# SZG-TEMPLATE-TXR.net
KiCad netlist of a schematic drawn in Altium Designer
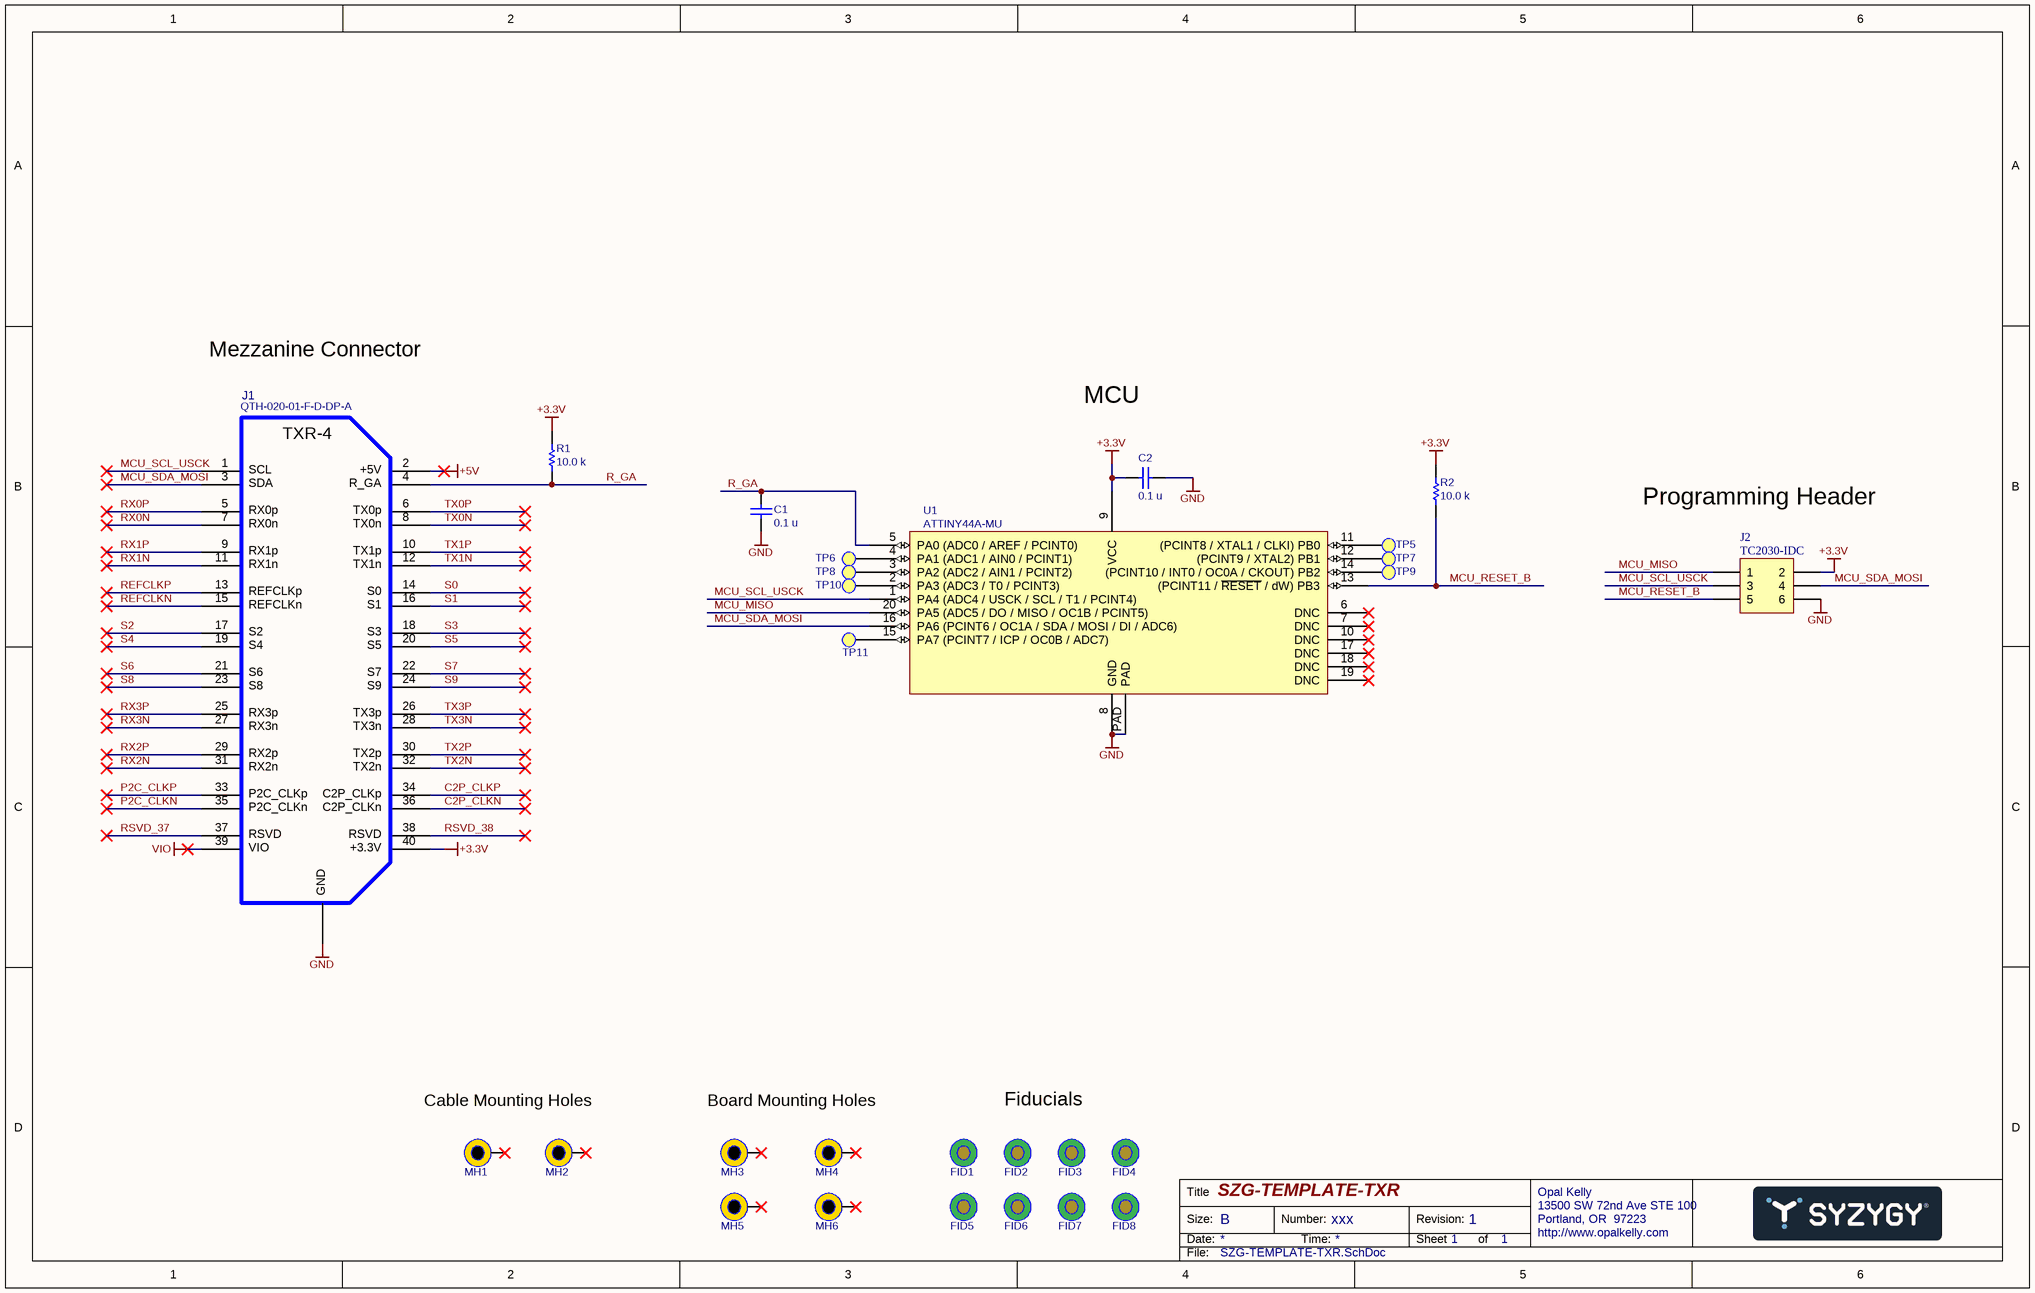
[diagram p0: SZG-TEMPLATE-TXR.SchDoc]

(export (version "E")
  (design (tool "Eeschema 10.0.6"))
  (components
    (comp (ref "C1")
      (value "0.1 u")
      (footprint "CAPC1005X06N")
      (description "Ceramic capacitor")
      (fields (field (name "MANUFACTURER") "Kemet") (field (name "PARTNUMBER") "000070"))
      (libsource (lib "Aligni") (part "Capacitor"))
    )
    (comp (ref "C2")
      (value "0.1 u")
      (footprint "CAPC1005X06N")
      (description "Ceramic capacitor")
      (fields (field (name "MANUFACTURER") "Kemet") (field (name "PARTNUMBER") "000070"))
      (libsource (lib "Aligni") (part "Capacitor"))
    )
    (comp (ref "FID1")
      (value "FIDUCIAL")
      (footprint "FID1MM/2MM-SS")
      (description "PCB fiducial")
      (libsource (lib "NoBOM") (part "FIDUCIAL"))
    )
    (comp (ref "FID2")
      (value "FIDUCIAL")
      (footprint "FID1MM/2MM-SS")
      (description "PCB fiducial")
      (libsource (lib "NoBOM") (part "FIDUCIAL"))
    )
    (comp (ref "FID3")
      (value "FIDUCIAL")
      (footprint "FID1MM/2MM-SS")
      (description "PCB fiducial")
      (libsource (lib "NoBOM") (part "FIDUCIAL"))
    )
    (comp (ref "FID4")
      (value "FIDUCIAL")
      (footprint "FID1MM/2MM-SS")
      (description "PCB fiducial")
      (libsource (lib "NoBOM") (part "FIDUCIAL"))
    )
    (comp (ref "FID5")
      (value "FIDUCIAL")
      (footprint "FID1MM/2MM-SS")
      (description "PCB fiducial")
      (libsource (lib "NoBOM") (part "FIDUCIAL"))
    )
    (comp (ref "FID6")
      (value "FIDUCIAL")
      (footprint "FID1MM/2MM-SS")
      (description "PCB fiducial")
      (libsource (lib "NoBOM") (part "FIDUCIAL"))
    )
    (comp (ref "FID7")
      (value "FIDUCIAL")
      (footprint "FID1MM/2MM-SS")
      (description "PCB fiducial")
      (libsource (lib "NoBOM") (part "FIDUCIAL"))
    )
    (comp (ref "FID8")
      (value "FIDUCIAL")
      (footprint "FID1MM/2MM-SS")
      (description "PCB fiducial")
      (libsource (lib "NoBOM") (part "FIDUCIAL"))
    )
    (comp (ref "J1")
      (value "40-pin, ground protection in middle")
      (footprint "QTH-020-01-X-D-DP-A-L")
      (description "0.5mm hi-speed, high-density header (female)")
      (fields
        (field (name "MANUFACTURER") "Samtec")
        (field (name "MANUFACTURER_PN") "QTH-020-01-F-D-DP-A")
        (field (name "ALIGNIPARTNUMBER") "001605")
      )
      (libsource (lib "Aligni") (part "QTH-DP_QSH-DP-020"))
    )
    (comp (ref "J2")
      (value "~")
      (footprint "TC2030-DUAL")
      (description "Tag-Connect 6-pin Plug-of-Nails spring-pin cable footprint")
      (fields
        (field (name "ALIGNIPARTNUMBER") "002062")
        (field (name "MANUFACTURER") "Tag-Connect")
        (field (name "MANUFACTURER_PN") "TC2030-IDC")
      )
      (libsource (lib "Aligni") (part "Header 3X2"))
    )
    (comp (ref "MH1")
      (value "MTG")
      (footprint "MTG-3.2/6.5-PTH")
      (description "Mounting hole")
      (libsource (lib "NoBOM") (part "MTG"))
    )
    (comp (ref "MH2")
      (value "MTG")
      (footprint "MTG-3.2/6.5-PTH")
      (description "Mounting hole")
      (libsource (lib "NoBOM") (part "MTG"))
    )
    (comp (ref "MH3")
      (value "MTG")
      (footprint "MTG-3.2/6.5-PTH")
      (description "Mounting hole")
      (libsource (lib "NoBOM") (part "MTG"))
    )
    (comp (ref "MH4")
      (value "MTG")
      (footprint "MTG-3.2/6.5-PTH")
      (description "Mounting hole")
      (libsource (lib "NoBOM") (part "MTG"))
    )
    (comp (ref "MH5")
      (value "MTG")
      (footprint "MTG-3.2/6.5-PTH")
      (description "Mounting hole")
      (libsource (lib "NoBOM") (part "MTG"))
    )
    (comp (ref "MH6")
      (value "MTG")
      (footprint "MTG-3.2/6.5-PTH")
      (description "Mounting hole")
      (libsource (lib "NoBOM") (part "MTG"))
    )
    (comp (ref "R1")
      (value "10.0 k")
      (footprint "RESC1005X06N")
      (description "Thick-film resistor")
      (fields (field (name "MANUFACTURER") "Vishay") (field (name "PARTNUMBER") "001521"))
      (libsource (lib "Aligni") (part "Resistor"))
    )
    (comp (ref "R2")
      (value "10.0 k")
      (footprint "RESC1005X06N")
      (description "Thick-film resistor")
      (fields (field (name "MANUFACTURER") "Vishay") (field (name "PARTNUMBER") "001521"))
      (libsource (lib "Aligni") (part "Resistor"))
    )
    (comp (ref "TP5")
      (value "TESTPOINT-SMD20")
      (footprint "TP-SMD20")
      (description "Test point, surface-mount, 20mil")
      (libsource (lib "NoBOM") (part "TESTPOINT-SMD20"))
    )
    (comp (ref "TP6")
      (value "TESTPOINT-SMD20")
      (footprint "TP-SMD20")
      (description "Test point, surface-mount, 20mil")
      (libsource (lib "NoBOM") (part "TESTPOINT-SMD20"))
    )
    (comp (ref "TP7")
      (value "TESTPOINT-SMD20")
      (footprint "TP-SMD20")
      (description "Test point, surface-mount, 20mil")
      (libsource (lib "NoBOM") (part "TESTPOINT-SMD20"))
    )
    (comp (ref "TP8")
      (value "TESTPOINT-SMD20")
      (footprint "TP-SMD20")
      (description "Test point, surface-mount, 20mil")
      (libsource (lib "NoBOM") (part "TESTPOINT-SMD20"))
    )
    (comp (ref "TP9")
      (value "TESTPOINT-SMD20")
      (footprint "TP-SMD20")
      (description "Test point, surface-mount, 20mil")
      (libsource (lib "NoBOM") (part "TESTPOINT-SMD20"))
    )
    (comp (ref "TP10")
      (value "TESTPOINT-SMD20")
      (footprint "TP-SMD20")
      (description "Test point, surface-mount, 20mil")
      (libsource (lib "NoBOM") (part "TESTPOINT-SMD20"))
    )
    (comp (ref "TP11")
      (value "TESTPOINT-SMD20")
      (footprint "TP-SMD20")
      (description "Test point, surface-mount, 20mil")
      (libsource (lib "NoBOM") (part "TESTPOINT-SMD20"))
    )
    (comp (ref "U1")
      (value "ATTINY44A-MU")
      (footprint "QFN-EP-20")
      (description "8-bit MCU, 4 KB flash, 256 bytes EEPROM")
      (fields (field (name "MANUFACTURER") "Microchip") (field (name "PARTNUMBER") "001552"))
      (libsource (lib "Aligni") (part "ATTINYx4A-MU"))
    )
  )
  (nets
    (net (code "1") (name "+3.3V") (class "Default")
      (node (ref "C2") (pin "2") (pinfunction "2_2") (pintype "passive"))
      (node (ref "J1") (pin "40") (pinfunction "40_40") (pintype "passive"))
      (node (ref "J2") (pin "2") (pinfunction "2_2") (pintype "passive"))
      (node (ref "R1") (pin "2") (pinfunction "2_2") (pintype "passive"))
      (node (ref "R2") (pin "2") (pinfunction "2_2") (pintype "passive"))
      (node (ref "U1") (pin "9") (pinfunction "VCC_9") (pintype "power_in"))
    )
    (net (code "2") (name "+5V") (class "Default")
      (node (ref "J1") (pin "2") (pinfunction "2_2") (pintype "passive"))
    )
    (net (code "3") (name "/C2P_CLKN") (class "Default")
      (node (ref "J1") (pin "36") (pinfunction "36_36") (pintype "passive+no_connect"))
    )
    (net (code "4") (name "/C2P_CLKP") (class "Default")
      (node (ref "J1") (pin "34") (pinfunction "34_34") (pintype "passive+no_connect"))
    )
    (net (code "5") (name "/MCU_MISO") (class "Default")
      (node (ref "J2") (pin "1") (pinfunction "1_1") (pintype "passive"))
      (node (ref "U1") (pin "20") (pinfunction "PA5_(ADC5_/_DO_/_MISO_/_OC1B_/_PCINT5)_20") (pintype "bidirectional"))
    )
    (net (code "6") (name "/MCU_RESET_B") (class "Default")
      (node (ref "J2") (pin "5") (pinfunction "5_5") (pintype "passive"))
      (node (ref "R2") (pin "1") (pinfunction "1_1") (pintype "passive"))
      (node (ref "U1") (pin "13") (pinfunction "(PCINT11_/_~{RESET}_/_dW)_PB3_13") (pintype "bidirectional"))
    )
    (net (code "7") (name "/MCU_SCL_USCK") (class "Default")
      (node (ref "J1") (pin "1") (pinfunction "1_1") (pintype "passive"))
      (node (ref "J2") (pin "3") (pinfunction "3_3") (pintype "passive"))
      (node (ref "U1") (pin "1") (pinfunction "PA4_(ADC4_/_USCK_/_SCL_/_T1_/_PCINT4)_1") (pintype "bidirectional"))
    )
    (net (code "8") (name "/MCU_SDA_MOSI") (class "Default")
      (node (ref "J1") (pin "3") (pinfunction "3_3") (pintype "passive"))
      (node (ref "J2") (pin "4") (pinfunction "4_4") (pintype "passive"))
      (node (ref "U1") (pin "16") (pinfunction "PA6_(PCINT6_/_OC1A_/_SDA_/_MOSI_/_DI_/_ADC6)_16") (pintype "bidirectional"))
    )
    (net (code "9") (name "/P2C_CLKN") (class "Default")
      (node (ref "J1") (pin "35") (pinfunction "35_35") (pintype "passive+no_connect"))
    )
    (net (code "10") (name "/P2C_CLKP") (class "Default")
      (node (ref "J1") (pin "33") (pinfunction "33_33") (pintype "passive+no_connect"))
    )
    (net (code "11") (name "/REFCLKN") (class "Default")
      (node (ref "J1") (pin "15") (pinfunction "15_15") (pintype "passive+no_connect"))
    )
    (net (code "12") (name "/REFCLKP") (class "Default")
      (node (ref "J1") (pin "13") (pinfunction "13_13") (pintype "passive+no_connect"))
    )
    (net (code "13") (name "/RSVD_37") (class "Default")
      (node (ref "J1") (pin "37") (pinfunction "37_37") (pintype "passive+no_connect"))
    )
    (net (code "14") (name "/RSVD_38") (class "Default")
      (node (ref "J1") (pin "38") (pinfunction "38_38") (pintype "passive+no_connect"))
    )
    (net (code "15") (name "/RX0N") (class "Default")
      (node (ref "J1") (pin "7") (pinfunction "7_7") (pintype "passive+no_connect"))
    )
    (net (code "16") (name "/RX0P") (class "Default")
      (node (ref "J1") (pin "5") (pinfunction "5_5") (pintype "passive+no_connect"))
    )
    (net (code "17") (name "/RX1N") (class "Default")
      (node (ref "J1") (pin "11") (pinfunction "11_11") (pintype "passive+no_connect"))
    )
    (net (code "18") (name "/RX1P") (class "Default")
      (node (ref "J1") (pin "9") (pinfunction "9_9") (pintype "passive+no_connect"))
    )
    (net (code "19") (name "/RX2N") (class "Default")
      (node (ref "J1") (pin "31") (pinfunction "31_31") (pintype "passive+no_connect"))
    )
    (net (code "20") (name "/RX2P") (class "Default")
      (node (ref "J1") (pin "29") (pinfunction "29_29") (pintype "passive+no_connect"))
    )
    (net (code "21") (name "/RX3N") (class "Default")
      (node (ref "J1") (pin "27") (pinfunction "27_27") (pintype "passive+no_connect"))
    )
    (net (code "22") (name "/RX3P") (class "Default")
      (node (ref "J1") (pin "25") (pinfunction "25_25") (pintype "passive+no_connect"))
    )
    (net (code "23") (name "/R_GA") (class "Default")
      (node (ref "C1") (pin "2") (pinfunction "2_2") (pintype "passive"))
      (node (ref "J1") (pin "4") (pinfunction "4_4") (pintype "passive"))
      (node (ref "R1") (pin "1") (pinfunction "1_1") (pintype "passive"))
      (node (ref "U1") (pin "5") (pinfunction "PA0_(ADC0_/_AREF_/_PCINT0)_5") (pintype "bidirectional"))
    )
    (net (code "24") (name "/S0") (class "Default")
      (node (ref "J1") (pin "14") (pinfunction "14_14") (pintype "passive+no_connect"))
    )
    (net (code "25") (name "/S1") (class "Default")
      (node (ref "J1") (pin "16") (pinfunction "16_16") (pintype "passive+no_connect"))
    )
    (net (code "26") (name "/S2") (class "Default")
      (node (ref "J1") (pin "17") (pinfunction "17_17") (pintype "passive+no_connect"))
    )
    (net (code "27") (name "/S3") (class "Default")
      (node (ref "J1") (pin "18") (pinfunction "18_18") (pintype "passive+no_connect"))
    )
    (net (code "28") (name "/S4") (class "Default")
      (node (ref "J1") (pin "19") (pinfunction "19_19") (pintype "passive+no_connect"))
    )
    (net (code "29") (name "/S5") (class "Default")
      (node (ref "J1") (pin "20") (pinfunction "20_20") (pintype "passive+no_connect"))
    )
    (net (code "30") (name "/S6") (class "Default")
      (node (ref "J1") (pin "21") (pinfunction "21_21") (pintype "passive+no_connect"))
    )
    (net (code "31") (name "/S7") (class "Default")
      (node (ref "J1") (pin "22") (pinfunction "22_22") (pintype "passive+no_connect"))
    )
    (net (code "32") (name "/S8") (class "Default")
      (node (ref "J1") (pin "23") (pinfunction "23_23") (pintype "passive+no_connect"))
    )
    (net (code "33") (name "/S9") (class "Default")
      (node (ref "J1") (pin "24") (pinfunction "24_24") (pintype "passive+no_connect"))
    )
    (net (code "34") (name "/TX0N") (class "Default")
      (node (ref "J1") (pin "8") (pinfunction "8_8") (pintype "passive+no_connect"))
    )
    (net (code "35") (name "/TX0P") (class "Default")
      (node (ref "J1") (pin "6") (pinfunction "6_6") (pintype "passive+no_connect"))
    )
    (net (code "36") (name "/TX1N") (class "Default")
      (node (ref "J1") (pin "12") (pinfunction "12_12") (pintype "passive+no_connect"))
    )
    (net (code "37") (name "/TX1P") (class "Default")
      (node (ref "J1") (pin "10") (pinfunction "10_10") (pintype "passive+no_connect"))
    )
    (net (code "38") (name "/TX2N") (class "Default")
      (node (ref "J1") (pin "32") (pinfunction "32_32") (pintype "passive+no_connect"))
    )
    (net (code "39") (name "/TX2P") (class "Default")
      (node (ref "J1") (pin "30") (pinfunction "30_30") (pintype "passive+no_connect"))
    )
    (net (code "40") (name "/TX3N") (class "Default")
      (node (ref "J1") (pin "28") (pinfunction "28_28") (pintype "passive+no_connect"))
    )
    (net (code "41") (name "/TX3P") (class "Default")
      (node (ref "J1") (pin "26") (pinfunction "26_26") (pintype "passive+no_connect"))
    )
    (net (code "42") (name "GND") (class "Default")
      (node (ref "C1") (pin "1") (pinfunction "1_1") (pintype "passive"))
      (node (ref "C2") (pin "1") (pinfunction "1_1") (pintype "passive"))
      (node (ref "J1") (pin "0") (pinfunction "GND_0") (pintype "passive"))
      (node (ref "J2") (pin "6") (pinfunction "6_6") (pintype "passive"))
      (node (ref "U1") (pin "8") (pinfunction "GND_8") (pintype "power_in"))
      (node (ref "U1") (pin "PAD") (pinfunction "PAD_PAD") (pintype "power_in"))
    )
    (net (code "43") (name "Net-(TP5-PIN)") (class "Default")
      (node (ref "TP5") (pin "1") (pinfunction "PIN_1") (pintype "passive"))
      (node (ref "U1") (pin "11") (pinfunction "(PCINT8_/_XTAL1_/_CLKI)_PB0_11") (pintype "bidirectional"))
    )
    (net (code "44") (name "Net-(TP6-PIN)") (class "Default")
      (node (ref "TP6") (pin "1") (pinfunction "PIN_1") (pintype "passive"))
      (node (ref "U1") (pin "4") (pinfunction "PA1_(ADC1_/_AIN0_/_PCINT1)_4") (pintype "bidirectional"))
    )
    (net (code "45") (name "Net-(TP7-PIN)") (class "Default")
      (node (ref "TP7") (pin "1") (pinfunction "PIN_1") (pintype "passive"))
      (node (ref "U1") (pin "12") (pinfunction "(PCINT9_/_XTAL2)_PB1_12") (pintype "bidirectional"))
    )
    (net (code "46") (name "Net-(TP8-PIN)") (class "Default")
      (node (ref "TP8") (pin "1") (pinfunction "PIN_1") (pintype "passive"))
      (node (ref "U1") (pin "3") (pinfunction "PA2_(ADC2_/_AIN1_/_PCINT2)_3") (pintype "bidirectional"))
    )
    (net (code "47") (name "Net-(TP9-PIN)") (class "Default")
      (node (ref "TP9") (pin "1") (pinfunction "PIN_1") (pintype "passive"))
      (node (ref "U1") (pin "14") (pinfunction "(PCINT10_/_INT0_/_OC0A_/_CKOUT)_PB2_14") (pintype "bidirectional"))
    )
    (net (code "48") (name "Net-(TP10-PIN)") (class "Default")
      (node (ref "TP10") (pin "1") (pinfunction "PIN_1") (pintype "passive"))
      (node (ref "U1") (pin "2") (pinfunction "PA3_(ADC3_/_T0_/_PCINT3)_2") (pintype "bidirectional"))
    )
    (net (code "49") (name "Net-(TP11-PIN)") (class "Default")
      (node (ref "TP11") (pin "1") (pinfunction "PIN_1") (pintype "passive"))
      (node (ref "U1") (pin "15") (pinfunction "PA7_(PCINT7_/_ICP_/_OC0B_/_ADC7)_15") (pintype "bidirectional"))
    )
    (net (code "50") (name "VIO") (class "Default")
      (node (ref "J1") (pin "39") (pinfunction "39_39") (pintype "passive"))
    )
    (net (code "51") (name "unconnected-(MH1-Pad1)") (class "Default")
      (node (ref "MH1") (pin "1") (pinfunction "1_1") (pintype "passive+no_connect"))
    )
    (net (code "52") (name "unconnected-(MH2-Pad1)") (class "Default")
      (node (ref "MH2") (pin "1") (pinfunction "1_1") (pintype "passive+no_connect"))
    )
    (net (code "53") (name "unconnected-(MH3-Pad1)") (class "Default")
      (node (ref "MH3") (pin "1") (pinfunction "1_1") (pintype "passive+no_connect"))
    )
    (net (code "54") (name "unconnected-(MH4-Pad1)") (class "Default")
      (node (ref "MH4") (pin "1") (pinfunction "1_1") (pintype "passive+no_connect"))
    )
    (net (code "55") (name "unconnected-(MH5-Pad1)") (class "Default")
      (node (ref "MH5") (pin "1") (pinfunction "1_1") (pintype "passive+no_connect"))
    )
    (net (code "56") (name "unconnected-(MH6-Pad1)") (class "Default")
      (node (ref "MH6") (pin "1") (pinfunction "1_1") (pintype "passive+no_connect"))
    )
    (net (code "57") (name "unconnected-(U1-DNC-Pad6)") (class "Default")
      (node (ref "U1") (pin "6") (pinfunction "DNC_6") (pintype "passive+no_connect"))
    )
    (net (code "58") (name "unconnected-(U1-DNC-Pad7)") (class "Default")
      (node (ref "U1") (pin "7") (pinfunction "DNC_7") (pintype "passive+no_connect"))
    )
    (net (code "59") (name "unconnected-(U1-DNC-Pad10)") (class "Default")
      (node (ref "U1") (pin "10") (pinfunction "DNC_10") (pintype "passive+no_connect"))
    )
    (net (code "60") (name "unconnected-(U1-DNC-Pad17)") (class "Default")
      (node (ref "U1") (pin "17") (pinfunction "DNC_17") (pintype "passive+no_connect"))
    )
    (net (code "61") (name "unconnected-(U1-DNC-Pad18)") (class "Default")
      (node (ref "U1") (pin "18") (pinfunction "DNC_18") (pintype "passive+no_connect"))
    )
    (net (code "62") (name "unconnected-(U1-DNC-Pad19)") (class "Default")
      (node (ref "U1") (pin "19") (pinfunction "DNC_19") (pintype "passive+no_connect"))
    )
  )
)
